# Sheet2.net
KiCad netlist of a schematic drawn in Altium Designer
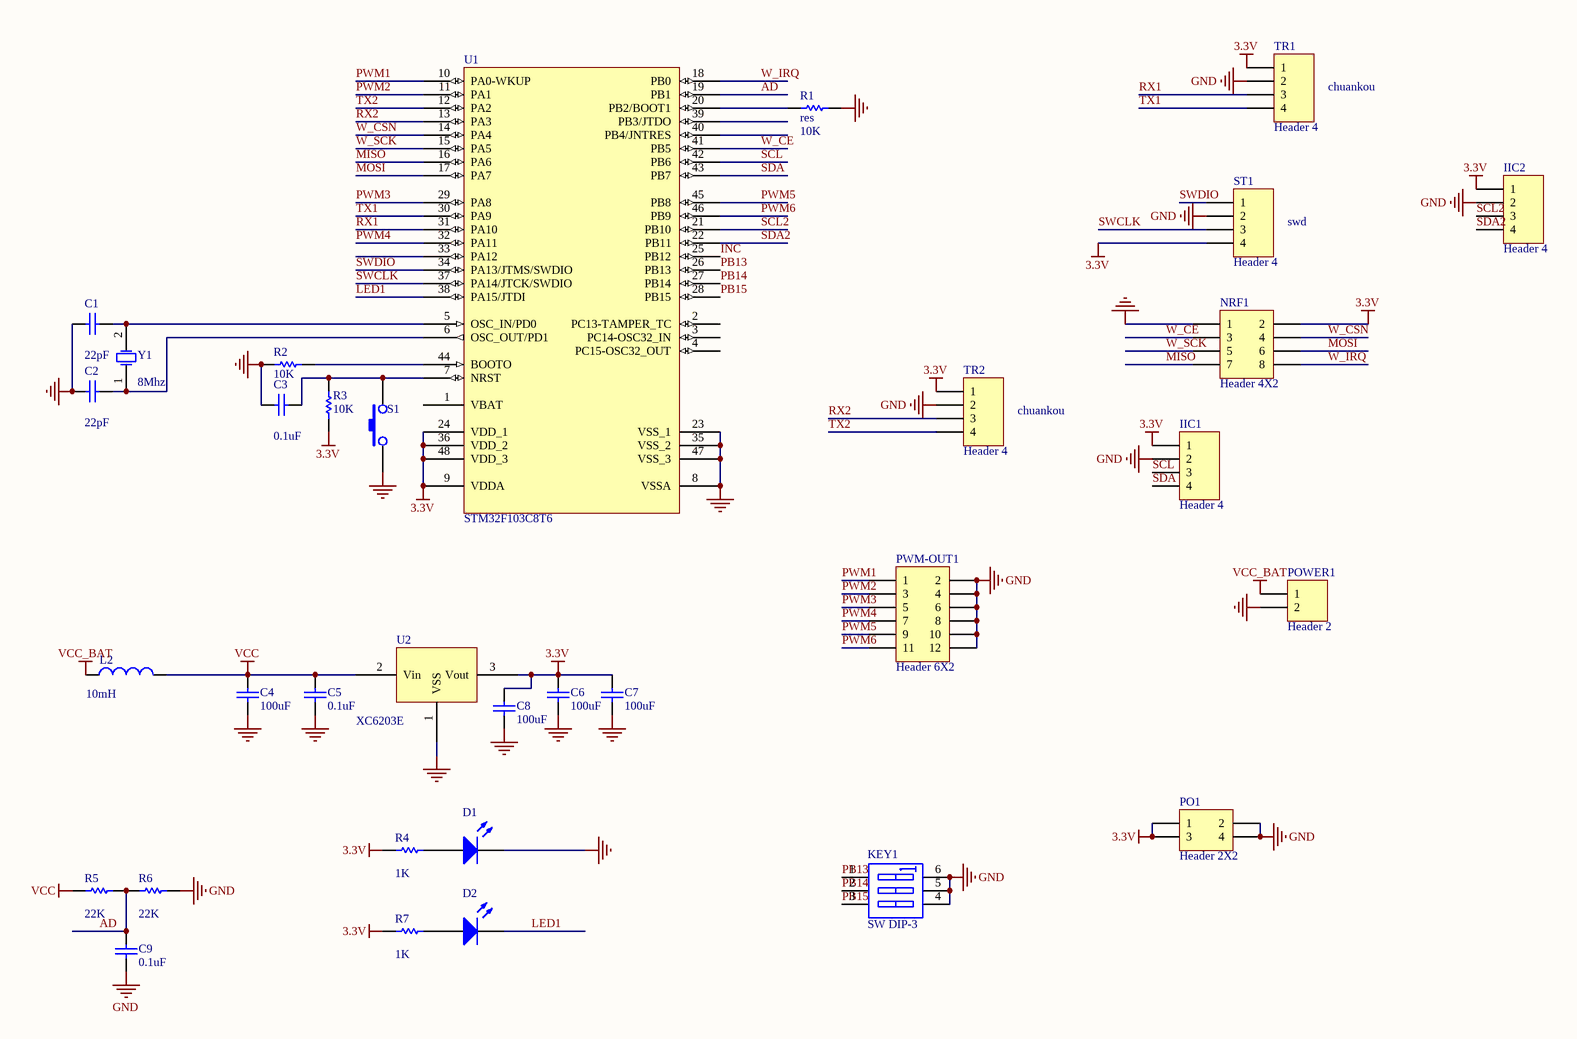
[diagram p0: Sheet2.SchDoc]

(export (version "E")
  (design (tool "Eeschema 10.0.6"))
  (components
    (comp (ref "C1")
      (value "22pF")
      (footprint "0603c")
      (fields (field (name "Comment") "cap"))
      (libsource (lib "bai") (part "cap"))
    )
    (comp (ref "C2")
      (value "22pF")
      (footprint "0603c")
      (fields (field (name "Comment") "cap"))
      (libsource (lib "bai") (part "cap"))
    )
    (comp (ref "C3")
      (value "0.1uF")
      (footprint "0603c")
      (fields (field (name "Comment") "cap"))
      (libsource (lib "bai") (part "cap"))
    )
    (comp (ref "C4")
      (value "100uF")
      (footprint "0603c")
      (fields (field (name "Comment") "cap"))
      (libsource (lib "bai") (part "cap"))
    )
    (comp (ref "C5")
      (value "0.1uF")
      (footprint "0603c")
      (fields (field (name "Comment") "cap"))
      (libsource (lib "bai") (part "cap"))
    )
    (comp (ref "C6")
      (value "100uF")
      (footprint "0603c")
      (fields (field (name "Comment") "cap"))
      (libsource (lib "bai") (part "cap"))
    )
    (comp (ref "C7")
      (value "100uF")
      (footprint "0603c")
      (fields (field (name "Comment") "cap"))
      (libsource (lib "bai") (part "cap"))
    )
    (comp (ref "C8")
      (value "100uF")
      (footprint "0603c")
      (fields (field (name "Comment") "cap"))
      (libsource (lib "bai") (part "cap"))
    )
    (comp (ref "C9")
      (value "0.1uF")
      (footprint "0603c")
      (fields (field (name "Comment") "cap"))
      (libsource (lib "bai") (part "cap"))
    )
    (comp (ref "D1")
      (value "LED0")
      (footprint "0603c")
      (description "Typical INFRARED GaAs LED")
      (fields (field (name "PUBLISHER") "Altium Limited"))
      (libsource (lib "Miscellaneous Devices") (part "LED0"))
    )
    (comp (ref "D2")
      (value "LED0")
      (footprint "0603c")
      (description "Typical INFRARED GaAs LED")
      (fields (field (name "PUBLISHER") "Altium Limited"))
      (libsource (lib "Miscellaneous Devices") (part "LED0"))
    )
    (comp (ref "IIC1")
      (value "Header 4")
      (footprint "HDR1X4")
      (description "Header, 4-Pin")
      (fields (field (name "PUBLISHER") "Altium Limited"))
      (libsource (lib "Miscellaneous Connectors") (part "Header 4"))
    )
    (comp (ref "IIC2")
      (value "Header 4")
      (footprint "HDR1X4")
      (description "Header, 4-Pin")
      (fields (field (name "PUBLISHER") "Altium Limited"))
      (libsource (lib "Miscellaneous Connectors") (part "Header 4"))
    )
    (comp (ref "KEY1")
      (value "SW DIP-3")
      (footprint "DIP6")
      (description "DIP Switch")
      (libsource (lib "开关") (part "SW DIP-3"))
    )
    (comp (ref "L2")
      (value "10mH")
      (footprint "0805")
      (fields (field (name "Comment") "Inductor"))
      (libsource (lib "bai") (part "Inductor"))
    )
    (comp (ref "NRF1")
      (value "Header 4X2")
      (footprint "HDR2X4")
      (description "Header, 4-Pin, Dual row")
      (fields (field (name "PUBLISHER") "Altium Limited"))
      (libsource (lib "Miscellaneous Connectors") (part "Header 4X2"))
    )
    (comp (ref "PO1")
      (value "Header 2X2")
      (footprint "HDR2X2")
      (description "Header, 2-Pin, Dual row")
      (fields (field (name "PUBLISHER") "Altium Limited"))
      (libsource (lib "Miscellaneous Connectors") (part "Header 2X2"))
    )
    (comp (ref "POWER1")
      (value "Header 2")
      (footprint "HDR1X2")
      (description "Header, 2-Pin")
      (fields (field (name "PUBLISHER") "Altium Limited"))
      (libsource (lib "Miscellaneous Connectors") (part "Header 2"))
    )
    (comp (ref "PWM-OUT1")
      (value "Header 6X2")
      (footprint "HDR2X6")
      (description "Header, 6-Pin, Dual row")
      (fields (field (name "PUBLISHER") "Altium Limited"))
      (libsource (lib "Miscellaneous Connectors") (part "Header 6X2"))
    )
    (comp (ref "R1")
      (value "res")
      (footprint "0603c")
      (fields (field (name "RES") "10K"))
      (libsource (lib "bai") (part "res"))
    )
    (comp (ref "R2")
      (value "res")
      (footprint "0603c")
      (fields (field (name "RES") "10K"))
      (libsource (lib "bai") (part "res"))
    )
    (comp (ref "R3")
      (value "res")
      (footprint "0603c")
      (fields (field (name "RES") "10K"))
      (libsource (lib "bai") (part "res"))
    )
    (comp (ref "R4")
      (value "res")
      (footprint "0603c")
      (fields (field (name "RES") "1K"))
      (libsource (lib "bai") (part "res"))
    )
    (comp (ref "R5")
      (value "res")
      (footprint "0603c")
      (fields (field (name "RES") "22K"))
      (libsource (lib "bai") (part "res"))
    )
    (comp (ref "R6")
      (value "res")
      (footprint "0603c")
      (fields (field (name "RES") "22K"))
      (libsource (lib "bai") (part "res"))
    )
    (comp (ref "R7")
      (value "res")
      (footprint "0603c")
      (fields (field (name "RES") "1K"))
      (libsource (lib "bai") (part "res"))
    )
    (comp (ref "S1") (value "~") (footprint "7243") (libsource (lib "开关") (part "微动开关")))
    (comp (ref "ST1")
      (value "Header 4")
      (footprint "HDR1X4")
      (description "Header, 4-Pin")
      (fields (field (name "PUBLISHER") "Altium Limited"))
      (libsource (lib "Miscellaneous Connectors") (part "Header 4"))
    )
    (comp (ref "TR1")
      (value "Header 4")
      (footprint "HDR1X4")
      (description "Header, 4-Pin")
      (fields (field (name "PUBLISHER") "Altium Limited"))
      (libsource (lib "Miscellaneous Connectors") (part "Header 4"))
    )
    (comp (ref "TR2")
      (value "Header 4")
      (footprint "HDR1X4")
      (description "Header, 4-Pin")
      (fields (field (name "PUBLISHER") "Altium Limited"))
      (libsource (lib "Miscellaneous Connectors") (part "Header 4"))
    )
    (comp (ref "U1")
      (value "STM32F103C8T6")
      (footprint "LQFP48S")
      (libsource (lib "bai") (part "STM32F103C8T6"))
    )
    (comp (ref "U2") (value "XC6203E") (footprint "SOT-89") (libsource (lib "文哥做的") (part "XC6203")))
    (comp (ref "Y1")
      (value "5032xtal")
      (footprint "XTAL")
      (fields (field (name "ALTIUM_UNNAMED_1") "8Mhz"))
      (libsource (lib "bai") (part "5032xtal"))
    )
  )
  (nets
    (net (code "1") (name "/AD") (class "Default")
      (node (ref "C9") (pin "2") (pinfunction "2_2") (pintype "passive"))
      (node (ref "R5") (pin "2") (pinfunction "2_2") (pintype "passive"))
      (node (ref "R6") (pin "1") (pinfunction "1_1") (pintype "passive"))
      (node (ref "U1") (pin "19") (pinfunction "PB1_19") (pintype "bidirectional"))
    )
    (net (code "2") (name "/INC") (class "Default")
      (node (ref "U1") (pin "25") (pinfunction "PB12_25") (pintype "bidirectional"))
    )
    (net (code "3") (name "/LED1") (class "Default")
      (node (ref "D2") (pin "2") (pinfunction "K_2") (pintype "passive"))
      (node (ref "U1") (pin "38") (pinfunction "PA15/JTDI_38") (pintype "bidirectional"))
    )
    (net (code "4") (name "/MISO") (class "Default")
      (node (ref "NRF1") (pin "7") (pinfunction "7_7") (pintype "passive"))
      (node (ref "U1") (pin "16") (pinfunction "PA6_16") (pintype "bidirectional"))
    )
    (net (code "5") (name "/MOSI") (class "Default")
      (node (ref "NRF1") (pin "6") (pinfunction "6_6") (pintype "passive"))
      (node (ref "U1") (pin "17") (pinfunction "PA7_17") (pintype "bidirectional"))
    )
    (net (code "6") (name "/PB13") (class "Default")
      (node (ref "KEY1") (pin "1") (pinfunction "A1_1") (pintype "passive"))
      (node (ref "U1") (pin "26") (pinfunction "PB13_26") (pintype "bidirectional"))
    )
    (net (code "7") (name "/PB14") (class "Default")
      (node (ref "KEY1") (pin "2") (pinfunction "A2_2") (pintype "passive"))
      (node (ref "U1") (pin "27") (pinfunction "PB14_27") (pintype "bidirectional"))
    )
    (net (code "8") (name "/PB15") (class "Default")
      (node (ref "KEY1") (pin "3") (pinfunction "A3_3") (pintype "passive"))
      (node (ref "U1") (pin "28") (pinfunction "PB15_28") (pintype "bidirectional"))
    )
    (net (code "9") (name "/PWM1") (class "Default")
      (node (ref "PWM-OUT1") (pin "1") (pinfunction "1_1") (pintype "passive"))
      (node (ref "U1") (pin "10") (pinfunction "PA0-WKUP_10") (pintype "bidirectional"))
    )
    (net (code "10") (name "/PWM2") (class "Default")
      (node (ref "PWM-OUT1") (pin "3") (pinfunction "3_3") (pintype "passive"))
      (node (ref "U1") (pin "11") (pinfunction "PA1_11") (pintype "bidirectional"))
    )
    (net (code "11") (name "/PWM3") (class "Default")
      (node (ref "PWM-OUT1") (pin "5") (pinfunction "5_5") (pintype "passive"))
      (node (ref "U1") (pin "29") (pinfunction "PA8_29") (pintype "bidirectional"))
    )
    (net (code "12") (name "/PWM4") (class "Default")
      (node (ref "PWM-OUT1") (pin "7") (pinfunction "7_7") (pintype "passive"))
      (node (ref "U1") (pin "32") (pinfunction "PA11_32") (pintype "bidirectional"))
    )
    (net (code "13") (name "/PWM5") (class "Default")
      (node (ref "PWM-OUT1") (pin "9") (pinfunction "9_9") (pintype "passive"))
      (node (ref "U1") (pin "45") (pinfunction "PB8_45") (pintype "bidirectional"))
    )
    (net (code "14") (name "/PWM6") (class "Default")
      (node (ref "PWM-OUT1") (pin "11") (pinfunction "11_11") (pintype "passive"))
      (node (ref "U1") (pin "46") (pinfunction "PB9_46") (pintype "bidirectional"))
    )
    (net (code "15") (name "/RX1") (class "Default")
      (node (ref "TR1") (pin "3") (pinfunction "3_3") (pintype "passive"))
      (node (ref "U1") (pin "31") (pinfunction "PA10_31") (pintype "bidirectional"))
    )
    (net (code "16") (name "/RX2") (class "Default")
      (node (ref "TR2") (pin "3") (pinfunction "3_3") (pintype "passive"))
      (node (ref "U1") (pin "13") (pinfunction "PA3_13") (pintype "bidirectional"))
    )
    (net (code "17") (name "/SCL") (class "Default")
      (node (ref "IIC1") (pin "3") (pinfunction "3_3") (pintype "passive"))
      (node (ref "U1") (pin "42") (pinfunction "PB6_42") (pintype "bidirectional"))
    )
    (net (code "18") (name "/SCL2") (class "Default")
      (node (ref "IIC2") (pin "3") (pinfunction "3_3") (pintype "passive"))
      (node (ref "U1") (pin "21") (pinfunction "PB10_21") (pintype "bidirectional"))
    )
    (net (code "19") (name "/SDA") (class "Default")
      (node (ref "IIC1") (pin "4") (pinfunction "4_4") (pintype "passive"))
      (node (ref "U1") (pin "43") (pinfunction "PB7_43") (pintype "bidirectional"))
    )
    (net (code "20") (name "/SDA2") (class "Default")
      (node (ref "IIC2") (pin "4") (pinfunction "4_4") (pintype "passive"))
      (node (ref "U1") (pin "22") (pinfunction "PB11_22") (pintype "bidirectional"))
    )
    (net (code "21") (name "/SWCLK") (class "Default")
      (node (ref "ST1") (pin "3") (pinfunction "3_3") (pintype "passive"))
      (node (ref "U1") (pin "37") (pinfunction "PA14/JTCK/SWDIO_37") (pintype "bidirectional"))
    )
    (net (code "22") (name "/SWDIO") (class "Default")
      (node (ref "ST1") (pin "1") (pinfunction "1_1") (pintype "passive"))
      (node (ref "U1") (pin "34") (pinfunction "PA13/JTMS/SWDIO_34") (pintype "bidirectional"))
    )
    (net (code "23") (name "/TX1") (class "Default")
      (node (ref "TR1") (pin "4") (pinfunction "4_4") (pintype "passive"))
      (node (ref "U1") (pin "30") (pinfunction "PA9_30") (pintype "bidirectional"))
    )
    (net (code "24") (name "/TX2") (class "Default")
      (node (ref "TR2") (pin "4") (pinfunction "4_4") (pintype "passive"))
      (node (ref "U1") (pin "12") (pinfunction "PA2_12") (pintype "bidirectional"))
    )
    (net (code "25") (name "/W_CE") (class "Default")
      (node (ref "NRF1") (pin "3") (pinfunction "3_3") (pintype "passive"))
      (node (ref "U1") (pin "41") (pinfunction "PB5_41") (pintype "bidirectional"))
    )
    (net (code "26") (name "/W_CSN") (class "Default")
      (node (ref "NRF1") (pin "4") (pinfunction "4_4") (pintype "passive"))
      (node (ref "U1") (pin "14") (pinfunction "PA4_14") (pintype "bidirectional"))
    )
    (net (code "27") (name "/W_IRQ") (class "Default")
      (node (ref "NRF1") (pin "8") (pinfunction "8_8") (pintype "passive"))
      (node (ref "U1") (pin "18") (pinfunction "PB0_18") (pintype "bidirectional"))
    )
    (net (code "28") (name "/W_SCK") (class "Default")
      (node (ref "NRF1") (pin "5") (pinfunction "5_5") (pintype "passive"))
      (node (ref "U1") (pin "15") (pinfunction "PA5_15") (pintype "bidirectional"))
    )
    (net (code "29") (name "3.3V") (class "Default")
      (node (ref "C6") (pin "2") (pinfunction "2_2") (pintype "passive"))
      (node (ref "C7") (pin "2") (pinfunction "2_2") (pintype "passive"))
      (node (ref "C8") (pin "2") (pinfunction "2_2") (pintype "passive"))
      (node (ref "IIC1") (pin "1") (pinfunction "1_1") (pintype "passive"))
      (node (ref "IIC2") (pin "1") (pinfunction "1_1") (pintype "passive"))
      (node (ref "NRF1") (pin "2") (pinfunction "2_2") (pintype "passive"))
      (node (ref "PO1") (pin "1") (pinfunction "1_1") (pintype "passive"))
      (node (ref "PO1") (pin "3") (pinfunction "3_3") (pintype "passive"))
      (node (ref "R3") (pin "1") (pinfunction "1_1") (pintype "passive"))
      (node (ref "R4") (pin "1") (pinfunction "1_1") (pintype "passive"))
      (node (ref "R7") (pin "1") (pinfunction "1_1") (pintype "passive"))
      (node (ref "ST1") (pin "4") (pinfunction "4_4") (pintype "passive"))
      (node (ref "TR1") (pin "1") (pinfunction "1_1") (pintype "passive"))
      (node (ref "TR2") (pin "1") (pinfunction "1_1") (pintype "passive"))
      (node (ref "U1") (pin "24") (pinfunction "VDD_1_24") (pintype "passive"))
      (node (ref "U1") (pin "36") (pinfunction "VDD_2_36") (pintype "passive"))
      (node (ref "U1") (pin "48") (pinfunction "VDD_3_48") (pintype "passive"))
      (node (ref "U1") (pin "9") (pinfunction "VDDA_9") (pintype "passive"))
      (node (ref "U2") (pin "3") (pinfunction "Vout_3") (pintype "passive"))
    )
    (net (code "30") (name "GND") (class "Default")
      (node (ref "C1") (pin "1") (pinfunction "1_1") (pintype "passive"))
      (node (ref "C2") (pin "1") (pinfunction "1_1") (pintype "passive"))
      (node (ref "C3") (pin "1") (pinfunction "1_1") (pintype "passive"))
      (node (ref "C4") (pin "1") (pinfunction "1_1") (pintype "passive"))
      (node (ref "C5") (pin "1") (pinfunction "1_1") (pintype "passive"))
      (node (ref "C6") (pin "1") (pinfunction "1_1") (pintype "passive"))
      (node (ref "C7") (pin "1") (pinfunction "1_1") (pintype "passive"))
      (node (ref "C8") (pin "1") (pinfunction "1_1") (pintype "passive"))
      (node (ref "C9") (pin "1") (pinfunction "1_1") (pintype "passive"))
      (node (ref "D1") (pin "2") (pinfunction "K_2") (pintype "passive"))
      (node (ref "IIC1") (pin "2") (pinfunction "2_2") (pintype "passive"))
      (node (ref "IIC2") (pin "2") (pinfunction "2_2") (pintype "passive"))
      (node (ref "KEY1") (pin "4") (pinfunction "B3_4") (pintype "passive"))
      (node (ref "KEY1") (pin "5") (pinfunction "B2_5") (pintype "passive"))
      (node (ref "KEY1") (pin "6") (pinfunction "B1_6") (pintype "passive"))
      (node (ref "NRF1") (pin "1") (pinfunction "1_1") (pintype "passive"))
      (node (ref "PO1") (pin "2") (pinfunction "2_2") (pintype "passive"))
      (node (ref "PO1") (pin "4") (pinfunction "4_4") (pintype "passive"))
      (node (ref "POWER1") (pin "2") (pinfunction "2_2") (pintype "passive"))
      (node (ref "PWM-OUT1") (pin "10") (pinfunction "10_10") (pintype "passive"))
      (node (ref "PWM-OUT1") (pin "12") (pinfunction "12_12") (pintype "passive"))
      (node (ref "PWM-OUT1") (pin "2") (pinfunction "2_2") (pintype "passive"))
      (node (ref "PWM-OUT1") (pin "4") (pinfunction "4_4") (pintype "passive"))
      (node (ref "PWM-OUT1") (pin "6") (pinfunction "6_6") (pintype "passive"))
      (node (ref "PWM-OUT1") (pin "8") (pinfunction "8_8") (pintype "passive"))
      (node (ref "R1") (pin "2") (pinfunction "2_2") (pintype "passive"))
      (node (ref "R2") (pin "1") (pinfunction "1_1") (pintype "passive"))
      (node (ref "R6") (pin "2") (pinfunction "2_2") (pintype "passive"))
      (node (ref "S1") (pin "1") (pinfunction "1_1") (pintype "passive"))
      (node (ref "ST1") (pin "2") (pinfunction "2_2") (pintype "passive"))
      (node (ref "TR1") (pin "2") (pinfunction "2_2") (pintype "passive"))
      (node (ref "TR2") (pin "2") (pinfunction "2_2") (pintype "passive"))
      (node (ref "U1") (pin "23") (pinfunction "VSS_1_23") (pintype "passive"))
      (node (ref "U1") (pin "35") (pinfunction "VSS_2_35") (pintype "passive"))
      (node (ref "U1") (pin "47") (pinfunction "VSS_3_47") (pintype "passive"))
      (node (ref "U1") (pin "8") (pinfunction "VSSA_8") (pintype "passive"))
      (node (ref "U2") (pin "1") (pinfunction "VSS_1") (pintype "passive"))
    )
    (net (code "31") (name "Net-(D1-A)") (class "Default")
      (node (ref "D1") (pin "1") (pinfunction "A_1") (pintype "passive"))
      (node (ref "R4") (pin "2") (pinfunction "2_2") (pintype "passive"))
    )
    (net (code "32") (name "Net-(D2-A)") (class "Default")
      (node (ref "D2") (pin "1") (pinfunction "A_1") (pintype "passive"))
      (node (ref "R7") (pin "2") (pinfunction "2_2") (pintype "passive"))
    )
    (net (code "33") (name "Net-(U1-BOOTO)") (class "Default")
      (node (ref "R2") (pin "2") (pinfunction "2_2") (pintype "passive"))
      (node (ref "U1") (pin "44") (pinfunction "BOOTO_44") (pintype "input"))
    )
    (net (code "34") (name "Net-(U1-NRST)") (class "Default")
      (node (ref "C3") (pin "2") (pinfunction "2_2") (pintype "passive"))
      (node (ref "R3") (pin "2") (pinfunction "2_2") (pintype "passive"))
      (node (ref "S1") (pin "2") (pinfunction "2_2") (pintype "passive"))
      (node (ref "U1") (pin "7") (pinfunction "NRST_7") (pintype "bidirectional"))
    )
    (net (code "35") (name "Net-(U1-OSC_IN{slash}PD0)") (class "Default")
      (node (ref "C1") (pin "2") (pinfunction "2_2") (pintype "passive"))
      (node (ref "U1") (pin "5") (pinfunction "OSC_IN/PD0_5") (pintype "input"))
      (node (ref "Y1") (pin "2") (pinfunction "OSC2_2") (pintype "passive"))
    )
    (net (code "36") (name "Net-(U1-OSC_OUT{slash}PD1)") (class "Default")
      (node (ref "C2") (pin "2") (pinfunction "2_2") (pintype "passive"))
      (node (ref "U1") (pin "6") (pinfunction "OSC_OUT/PD1_6") (pintype "output"))
      (node (ref "Y1") (pin "1") (pinfunction "OSC1_1") (pintype "passive"))
    )
    (net (code "37") (name "Net-(U1-PB2{slash}BOOT1)") (class "Default")
      (node (ref "R1") (pin "1") (pinfunction "1_1") (pintype "passive"))
      (node (ref "U1") (pin "20") (pinfunction "PB2/BOOT1_20") (pintype "bidirectional"))
    )
    (net (code "38") (name "VCC") (class "Default")
      (node (ref "C4") (pin "2") (pinfunction "2_2") (pintype "passive"))
      (node (ref "C5") (pin "2") (pinfunction "2_2") (pintype "passive"))
      (node (ref "L2") (pin "2") (pinfunction "2_2") (pintype "passive"))
      (node (ref "R5") (pin "1") (pinfunction "1_1") (pintype "passive"))
      (node (ref "U2") (pin "2") (pinfunction "Vin_2") (pintype "passive"))
    )
    (net (code "39") (name "VCC_BAT") (class "Default")
      (node (ref "L2") (pin "1") (pinfunction "1_1") (pintype "passive"))
      (node (ref "POWER1") (pin "1") (pinfunction "1_1") (pintype "passive"))
    )
    (net (code "40") (name "unconnected-(U1-PA12-Pad33)") (class "Default")
      (node (ref "U1") (pin "33") (pinfunction "PA12_33") (pintype "bidirectional"))
    )
    (net (code "41") (name "unconnected-(U1-PB3{slash}JTDO-Pad39)") (class "Default")
      (node (ref "U1") (pin "39") (pinfunction "PB3/JTDO_39") (pintype "bidirectional"))
    )
    (net (code "42") (name "unconnected-(U1-PB4{slash}JNTRES-Pad40)") (class "Default")
      (node (ref "U1") (pin "40") (pinfunction "PB4/JNTRES_40") (pintype "bidirectional"))
    )
    (net (code "43") (name "unconnected-(U1-PC13-TAMPER_TC-Pad2)") (class "Default")
      (node (ref "U1") (pin "2") (pinfunction "PC13-TAMPER_TC_2") (pintype "bidirectional"))
    )
    (net (code "44") (name "unconnected-(U1-PC14-OSC32_IN-Pad3)") (class "Default")
      (node (ref "U1") (pin "3") (pinfunction "PC14-OSC32_IN_3") (pintype "bidirectional"))
    )
    (net (code "45") (name "unconnected-(U1-PC15-OSC32_OUT-Pad4)") (class "Default")
      (node (ref "U1") (pin "4") (pinfunction "PC15-OSC32_OUT_4") (pintype "bidirectional"))
    )
    (net (code "46") (name "unconnected-(U1-VBAT-Pad1)") (class "Default")
      (node (ref "U1") (pin "1") (pinfunction "VBAT_1") (pintype "passive"))
    )
  )
)
